# living.net
KiCad netlist of a schematic drawn in Altium Designer
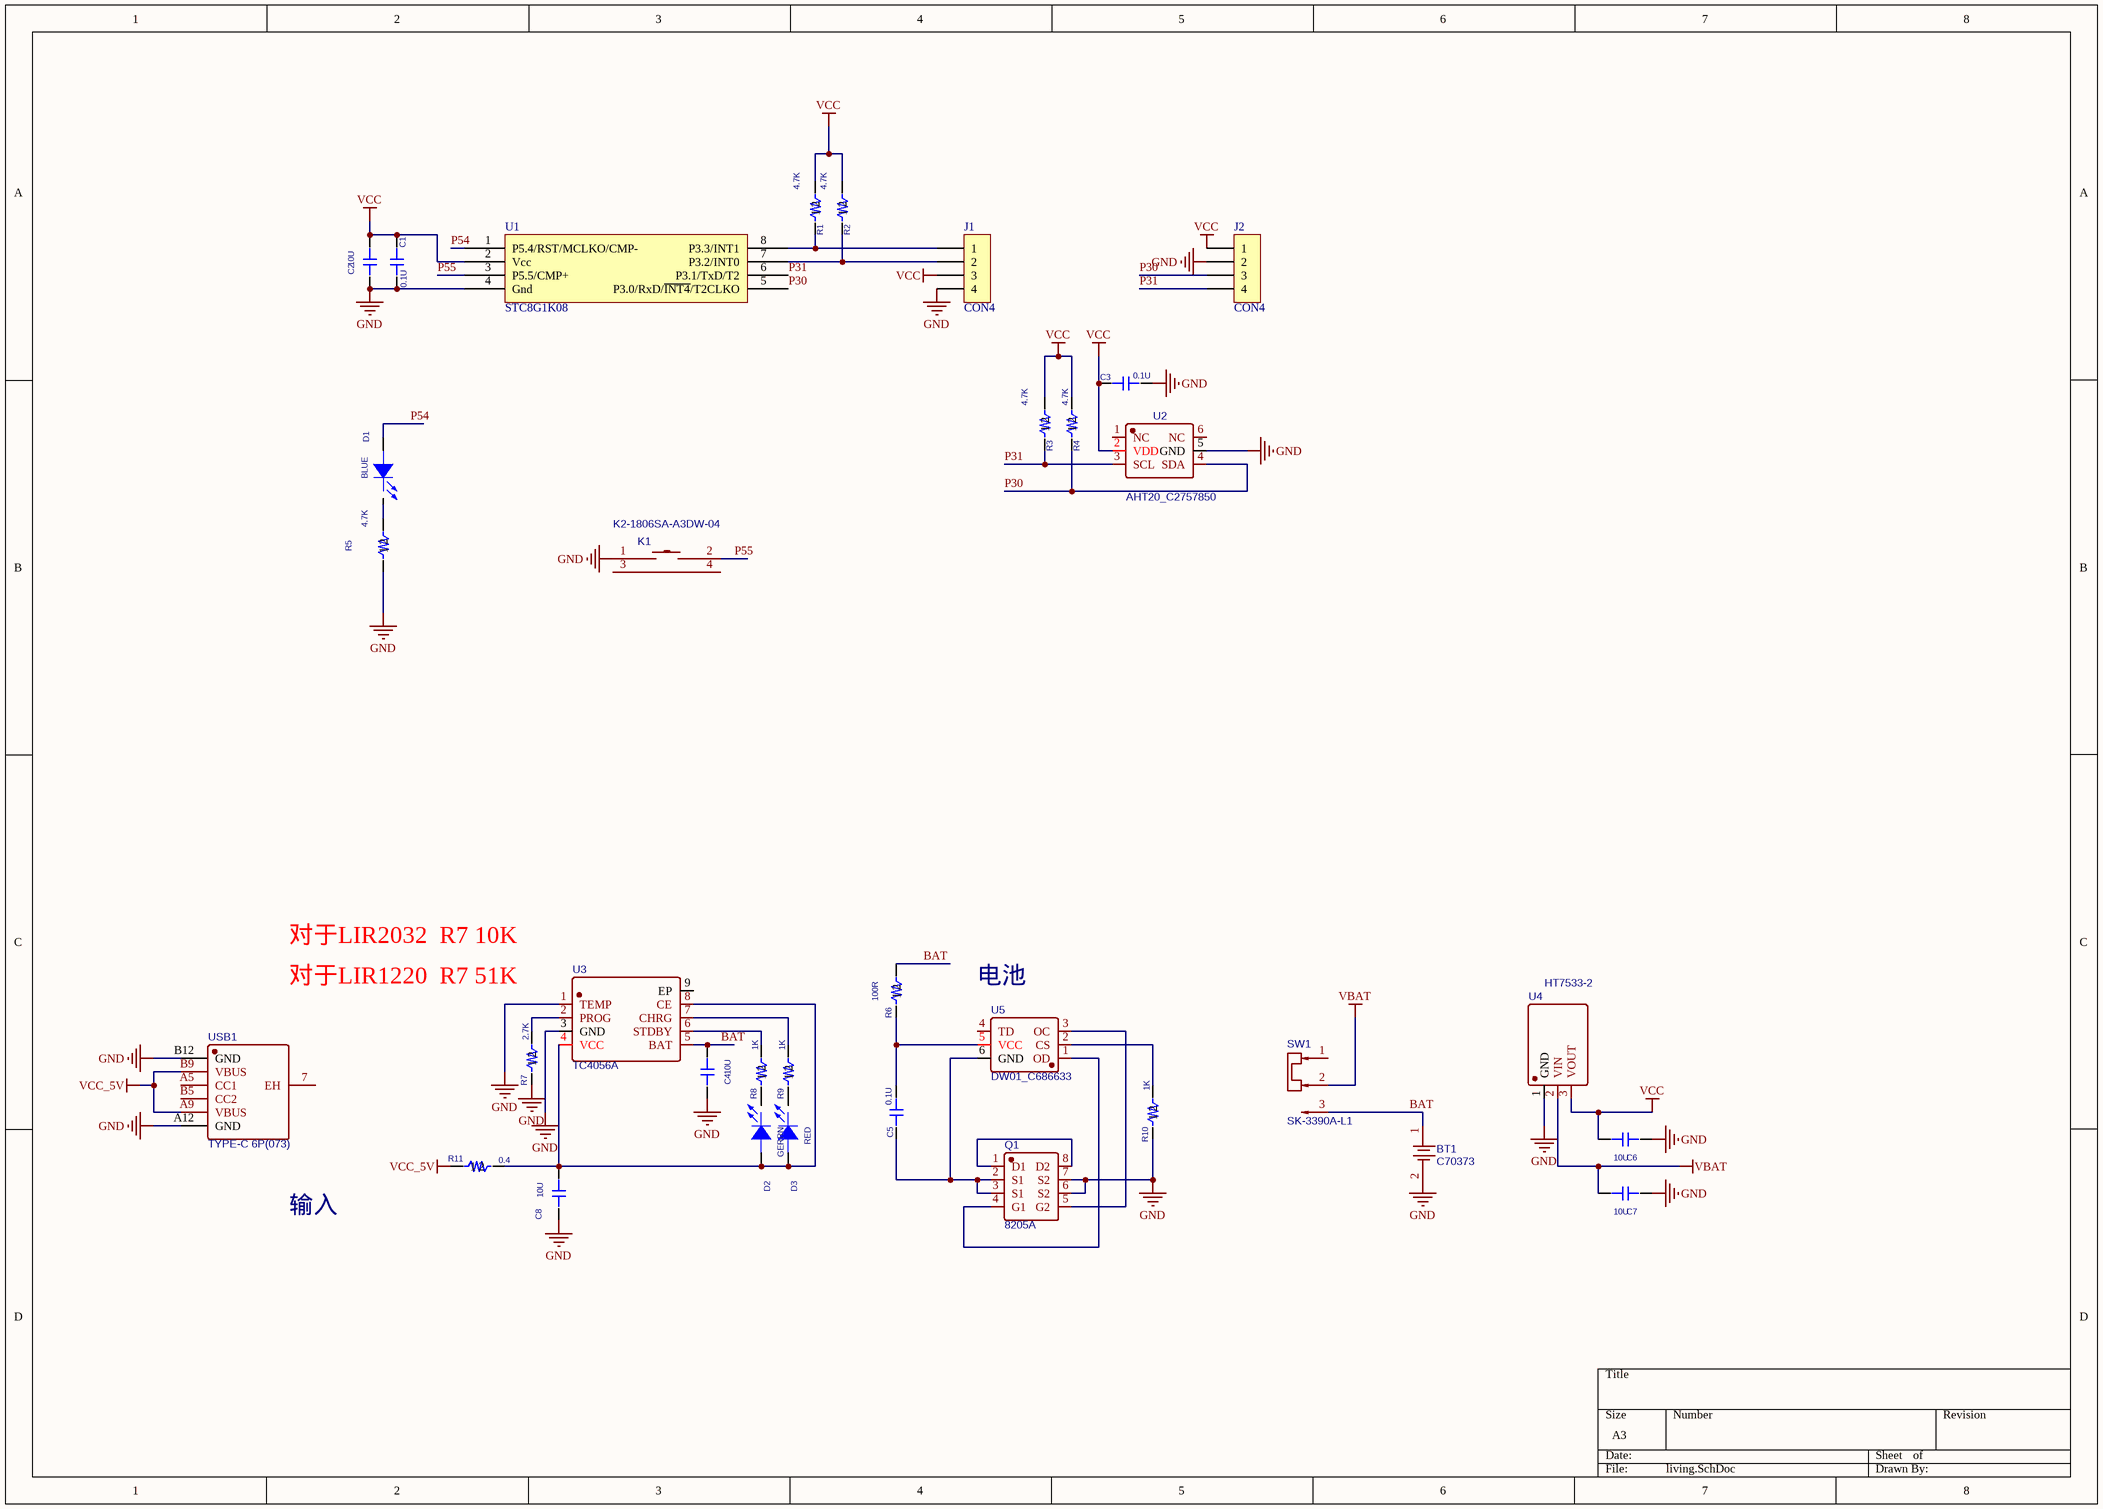
[diagram p0: living.SchDoc]

(export (version "E")
  (design (tool "Eeschema 10.0.6"))
  (components
    (comp (ref "BT1")
      (value "C70373")
      (footprint "BAT-SMD_CR2032-3V")
      (fields (field (name "CONTRIBUTOR") "LCSC"))
      (libsource (lib "CR2032") (part "C70373"))
    )
    (comp (ref "C1")
      (value "0.1U")
      (footprint "C_0603")
      (fields (field (name "Comment") "C_0.1UF_0603"))
      (libsource (lib "MINI-V3") (part "C_0.1UF_0603"))
    )
    (comp (ref "C2")
      (value "10U")
      (footprint "CAP_0603_FIRE")
      (fields (field (name "Comment") "C_10UF_0603"))
      (libsource (lib "MINI-V3") (part "C_10UF_0603"))
    )
    (comp (ref "C3")
      (value "0.1U")
      (footprint "C_0603")
      (fields (field (name "Comment") "C_0.1UF_0603"))
      (libsource (lib "MINI-V3") (part "C_0.1UF_0603"))
    )
    (comp (ref "C4")
      (value "10U")
      (footprint "CAP_0603_FIRE")
      (fields (field (name "Comment") "C_10UF_0603"))
      (libsource (lib "MINI-V3") (part "C_10UF_0603"))
    )
    (comp (ref "C5")
      (value "0.1U")
      (footprint "C_0603")
      (fields (field (name "Comment") "C_0.1UF_0603"))
      (libsource (lib "MINI-V3") (part "C_0.1UF_0603"))
    )
    (comp (ref "C6")
      (value "10U")
      (footprint "C_0603")
      (fields (field (name "Comment") "C_10UF_0603"))
      (libsource (lib "MINI-V3") (part "C_10UF_0603"))
    )
    (comp (ref "C7")
      (value "10U")
      (footprint "C_0603")
      (fields (field (name "Comment") "C_10UF_0603"))
      (libsource (lib "MINI-V3") (part "C_10UF_0603"))
    )
    (comp (ref "C8")
      (value "10U")
      (footprint "CAP_0603_FIRE")
      (fields (field (name "Comment") "C_10UF_0603"))
      (libsource (lib "MINI-V3") (part "C_10UF_0603"))
    )
    (comp (ref "D1")
      (value "BLUE")
      (footprint "LED_BLUE_0603_FIRE")
      (description "blue,0603")
      (fields (field (name "Comment") "LED_BLUE_0603_FIRE"))
      (libsource (lib "MINI-V3") (part "LED_BLUE_0603_FIRE"))
    )
    (comp (ref "D2")
      (value "GERRN")
      (footprint "LED_RED_0603_FIRE")
      (description "red,0805")
      (fields (field (name "Comment") "LED_RED_0603_FIRE"))
      (libsource (lib "MINI-V3") (part "LED_RED_0603_FIRE"))
    )
    (comp (ref "D3")
      (value "RED")
      (footprint "LED_RED_0603_FIRE")
      (description "red,0805")
      (fields (field (name "Comment") "LED_RED_0603_FIRE"))
      (libsource (lib "MINI-V3") (part "LED_RED_0603_FIRE"))
    )
    (comp (ref "J1")
      (value "CON4")
      (footprint "SIP-4")
      (description "Connector")
      (libsource (lib "CON系列") (part "CON4"))
    )
    (comp (ref "J2")
      (value "CON4")
      (footprint "SIP-4")
      (description "Connector")
      (libsource (lib "CON系列") (part "CON4"))
    )
    (comp (ref "K1")
      (value "K2-1806SA-A3DW-04")
      (footprint "KEY-SMD_K2-1806SA-AXXW-XX")
      (fields (field (name "BOM_SUPPLIER PART") "C2690015") (field (name "CONTRIBUTOR") "LCSC"))
      (libsource (lib "2_4_3.5按键") (part "K2-1806SA-A3DW-04"))
    )
    (comp (ref "Q1")
      (value "8205A")
      (footprint "TSSOP-8_L4.4-W3.0-P0.65-LS6.4-BL")
      (fields (field (name "BOM_SUPPLIER PART") "C181100") (field (name "CONTRIBUTOR") "LCSC"))
      (libsource (lib "8205A") (part "8205A"))
    )
    (comp (ref "R1")
      (value "4.7K")
      (footprint "RES_0603_FIRE")
      (description "0402")
      (fields (field (name "TOLERANCE") "+-5%") (field (name "Comment") "RES_4K7_0603_FIRE"))
      (libsource (lib "MINI-V3") (part "RES_4K7_0603_FIRE"))
    )
    (comp (ref "R2")
      (value "4.7K")
      (footprint "RES_0603_FIRE")
      (description "0402")
      (fields (field (name "TOLERANCE") "+-5%") (field (name "Comment") "RES_4K7_0603_FIRE"))
      (libsource (lib "MINI-V3") (part "RES_4K7_0603_FIRE"))
    )
    (comp (ref "R3")
      (value "4.7K")
      (footprint "RES_0603_FIRE")
      (description "0402")
      (fields (field (name "TOLERANCE") "+-5%") (field (name "Comment") "RES_4K7_0603_FIRE"))
      (libsource (lib "MINI-V3") (part "RES_4K7_0603_FIRE"))
    )
    (comp (ref "R4")
      (value "4.7K")
      (footprint "RES_0603_FIRE")
      (description "0402")
      (fields (field (name "TOLERANCE") "+-5%") (field (name "Comment") "RES_4K7_0603_FIRE"))
      (libsource (lib "MINI-V3") (part "RES_4K7_0603_FIRE"))
    )
    (comp (ref "R5")
      (value "4.7K")
      (footprint "RES_0603_FIRE")
      (description "0402")
      (fields (field (name "TOLERANCE") "+-5%") (field (name "Comment") "RES_4K7_0603_FIRE"))
      (libsource (lib "MINI-V3") (part "RES_4K7_0603_FIRE"))
    )
    (comp (ref "R6")
      (value "100R")
      (footprint "RES_0603_FIRE")
      (description "0402")
      (fields (field (name "TOLERANCE") "+-5%") (field (name "Comment") "RES_100R_0603_FIRE"))
      (libsource (lib "MINI-V3") (part "RES_100R_0603_FIRE"))
    )
    (comp (ref "R7")
      (value "2.7K")
      (footprint "R_0603")
      (fields (field (name "Comment") "R_2.7K_0603"))
      (libsource (lib "MINI-V3") (part "R_2.7K_0603"))
    )
    (comp (ref "R8")
      (value "1K")
      (footprint "RES_0603_FIRE")
      (description "0402")
      (fields (field (name "TOLERANCE") "+-5%") (field (name "Comment") "RES_1K_0603_FIRE"))
      (libsource (lib "MINI-V3") (part "RES_1K_0603_FIRE"))
    )
    (comp (ref "R9")
      (value "1K")
      (footprint "RES_0603_FIRE")
      (description "0402")
      (fields (field (name "TOLERANCE") "+-5%") (field (name "Comment") "RES_1K_0603_FIRE"))
      (libsource (lib "MINI-V3") (part "RES_1K_0603_FIRE"))
    )
    (comp (ref "R10")
      (value "1K")
      (footprint "RES_0603_FIRE")
      (description "0402")
      (fields (field (name "TOLERANCE") "+-5%") (field (name "Comment") "RES_1K_0603_FIRE"))
      (libsource (lib "MINI-V3") (part "RES_1K_0603_FIRE"))
    )
    (comp (ref "R11")
      (value "0.4")
      (footprint "R_0603")
      (fields (field (name "Comment") "R_2.7K_0603"))
      (libsource (lib "MINI-V3") (part "R_2.7K_0603"))
    )
    (comp (ref "SW1")
      (value "SK-3390A-L1")
      (footprint "SW-SMD_SK-3390A-L1")
      (fields (field (name "BOM_SUPPLIER PART") "C319018") (field (name "CONTRIBUTOR") "LCSC"))
      (libsource (lib "SK-3390A-L1") (part "SK-3390A-L1"))
    )
    (comp (ref "U1")
      (value "STC8G1K08")
      (footprint "SOP8")
      (libsource (lib "stcmcu_altium1819") (part "STC15W201S_SOP8"))
    )
    (comp (ref "U2")
      (value "AHT20_C2757850")
      (footprint "SENSOR-SMD_L3.0-W3.0-P1.00-BR")
      (fields
        (field (name "BOM_SUPPLIER PART") "C2757850")
        (field (name "BOM_MANUFACTURER PART") "AHT20")
        (field (name "CONTRIBUTOR") "LCSC")
      )
      (libsource (lib "AHT20") (part "AHT20_C2757850"))
    )
    (comp (ref "U3")
      (value "TC4056A")
      (footprint "SOP-8_L4.9-W3.9-P1.27-LS6.0-BL-EP")
      (fields (field (name "BOM_SUPPLIER PART") "C84051"))
      (libsource (lib "TC4056A") (part "TC4056A"))
    )
    (comp (ref "U4")
      (value "HT7533-2")
      (footprint "SOT-89-3_L4.5-W2.5-P1.50-LS4.2-BR")
      (fields (field (name "BOM_SUPPLIER PART") "C97849"))
      (libsource (lib "HT7533") (part "HT7533-2"))
    )
    (comp (ref "U5")
      (value "DW01_C686633")
      (footprint "SOT-23-6_L2.9-W1.6-P0.95-LS2.8-BR")
      (fields
        (field (name "BOM_SUPPLIER PART") "C686633")
        (field (name "BOM_MANUFACTURER PART") "DW01")
        (field (name "CONTRIBUTOR") "LCSC")
      )
      (libsource (lib "DW01") (part "DW01_C686633"))
    )
    (comp (ref "USB1")
      (value "TYPE-C 6P(073)")
      (footprint "TYPE-C-SMD_TYPE-C-6P")
      (fields (field (name "BOM_SUPPLIER PART") "C668623") (field (name "CONTRIBUTOR") "LCSC"))
      (libsource (lib "TYPE-C 6P(073)") (part "TYPE-C 6P(073)"))
    )
  )
  (nets
    (net (code "1") (name "/BAT") (class "Default")
      (node (ref "BT1") (pin "1") (pinfunction "1_1") (pintype "passive"))
      (node (ref "C4") (pin "2") (pinfunction "2_2") (pintype "passive"))
      (node (ref "R6") (pin "2") (pinfunction "2_2") (pintype "passive"))
      (node (ref "SW1") (pin "3") (pinfunction "3_3") (pintype "passive"))
      (node (ref "U3") (pin "5") (pinfunction "BAT_5") (pintype "passive"))
    )
    (net (code "2") (name "/P30") (class "Default")
      (node (ref "J2") (pin "3") (pinfunction "3_3") (pintype "passive"))
      (node (ref "R4") (pin "1") (pinfunction "1_1") (pintype "passive"))
      (node (ref "U1") (pin "5") (pinfunction "P3.0/RxD/~{INT4}/T2CLKO_5") (pintype "passive"))
      (node (ref "U2") (pin "4") (pinfunction "SDA_4") (pintype "passive"))
    )
    (net (code "3") (name "/P31") (class "Default")
      (node (ref "J2") (pin "4") (pinfunction "4_4") (pintype "passive"))
      (node (ref "R3") (pin "1") (pinfunction "1_1") (pintype "passive"))
      (node (ref "U1") (pin "6") (pinfunction "P3.1/TxD/T2_6") (pintype "passive"))
      (node (ref "U2") (pin "3") (pinfunction "SCL_3") (pintype "passive"))
    )
    (net (code "4") (name "/P54") (class "Default")
      (node (ref "D1") (pin "A") (pinfunction "ANODE_A") (pintype "passive"))
      (node (ref "U1") (pin "1") (pinfunction "P5.4/RST/MCLKO/CMP-_1") (pintype "passive"))
    )
    (net (code "5") (name "/P55") (class "Default")
      (node (ref "K1") (pin "2") (pinfunction "2_2") (pintype "passive"))
      (node (ref "U1") (pin "3") (pinfunction "P5.5/CMP+_3") (pintype "passive"))
    )
    (net (code "6") (name "GND") (class "Default")
      (node (ref "BT1") (pin "2") (pinfunction "2_2") (pintype "passive"))
      (node (ref "C1") (pin "2") (pinfunction "2_2") (pintype "passive"))
      (node (ref "C2") (pin "1") (pinfunction "1_1") (pintype "passive"))
      (node (ref "C3") (pin "2") (pinfunction "2_2") (pintype "passive"))
      (node (ref "C4") (pin "1") (pinfunction "1_1") (pintype "passive"))
      (node (ref "C6") (pin "1") (pinfunction "1_1") (pintype "passive"))
      (node (ref "C7") (pin "1") (pinfunction "1_1") (pintype "passive"))
      (node (ref "C8") (pin "1") (pinfunction "1_1") (pintype "passive"))
      (node (ref "J1") (pin "4") (pinfunction "4_4") (pintype "passive"))
      (node (ref "J2") (pin "2") (pinfunction "2_2") (pintype "passive"))
      (node (ref "K1") (pin "1") (pinfunction "1_1") (pintype "passive"))
      (node (ref "Q1") (pin "6") (pinfunction "S2_6") (pintype "passive"))
      (node (ref "Q1") (pin "7") (pinfunction "S2_7") (pintype "passive"))
      (node (ref "R10") (pin "1") (pinfunction "1_1") (pintype "passive"))
      (node (ref "R5") (pin "1") (pinfunction "1_1") (pintype "passive"))
      (node (ref "R7") (pin "1") (pinfunction "1_1") (pintype "passive"))
      (node (ref "U1") (pin "4") (pinfunction "Gnd_4") (pintype "passive"))
      (node (ref "U2") (pin "5") (pinfunction "GND_5") (pintype "passive"))
      (node (ref "U3") (pin "1") (pinfunction "TEMP_1") (pintype "passive"))
      (node (ref "U3") (pin "3") (pinfunction "GND_3") (pintype "passive"))
      (node (ref "U4") (pin "1") (pinfunction "GND_1") (pintype "passive"))
      (node (ref "USB1") (pin "A12") (pinfunction "GND_A12") (pintype "passive"))
      (node (ref "USB1") (pin "B12") (pinfunction "GND_B12") (pintype "passive"))
    )
    (net (code "7") (name "Net-(D1-CATHODE)") (class "Default")
      (node (ref "D1") (pin "K") (pinfunction "CATHODE_K") (pintype "passive"))
      (node (ref "R5") (pin "2") (pinfunction "2_2") (pintype "passive"))
    )
    (net (code "8") (name "Net-(D2-ANODE)") (class "Default")
      (node (ref "C8") (pin "2") (pinfunction "2_2") (pintype "passive"))
      (node (ref "D2") (pin "A") (pinfunction "ANODE_A") (pintype "passive"))
      (node (ref "D3") (pin "A") (pinfunction "ANODE_A") (pintype "passive"))
      (node (ref "R11") (pin "2") (pinfunction "2_2") (pintype "passive"))
      (node (ref "U3") (pin "4") (pinfunction "VCC_4") (pintype "passive"))
      (node (ref "U3") (pin "8") (pinfunction "CE_8") (pintype "passive"))
    )
    (net (code "9") (name "Net-(D2-CATHODE)") (class "Default")
      (node (ref "D2") (pin "K") (pinfunction "CATHODE_K") (pintype "passive"))
      (node (ref "R8") (pin "1") (pinfunction "1_1") (pintype "passive"))
    )
    (net (code "10") (name "Net-(D3-CATHODE)") (class "Default")
      (node (ref "D3") (pin "K") (pinfunction "CATHODE_K") (pintype "passive"))
      (node (ref "R9") (pin "1") (pinfunction "1_1") (pintype "passive"))
    )
    (net (code "11") (name "Net-(Q1-D1)") (class "Default")
      (node (ref "Q1") (pin "1") (pinfunction "D1_1") (pintype "passive"))
      (node (ref "Q1") (pin "8") (pinfunction "D2_8") (pintype "passive"))
    )
    (net (code "12") (name "Net-(Q1-G1)") (class "Default")
      (node (ref "Q1") (pin "4") (pinfunction "G1_4") (pintype "passive"))
      (node (ref "U5") (pin "1") (pinfunction "OD_1") (pintype "passive"))
    )
    (net (code "13") (name "Net-(Q1-G2)") (class "Default")
      (node (ref "Q1") (pin "5") (pinfunction "G2_5") (pintype "passive"))
      (node (ref "U5") (pin "3") (pinfunction "OC_3") (pintype "passive"))
    )
    (net (code "14") (name "Net-(U1-P3.2{slash}INT0)") (class "Default")
      (node (ref "J1") (pin "2") (pinfunction "2_2") (pintype "passive"))
      (node (ref "R2") (pin "1") (pinfunction "1_1") (pintype "passive"))
      (node (ref "U1") (pin "7") (pinfunction "P3.2/INT0_7") (pintype "passive"))
    )
    (net (code "15") (name "Net-(U1-P3.3{slash}INT1)") (class "Default")
      (node (ref "J1") (pin "1") (pinfunction "1_1") (pintype "passive"))
      (node (ref "R1") (pin "1") (pinfunction "1_1") (pintype "passive"))
      (node (ref "U1") (pin "8") (pinfunction "P3.3/INT1_8") (pintype "passive"))
    )
    (net (code "16") (name "Net-(U3-CHRG)") (class "Default")
      (node (ref "R9") (pin "2") (pinfunction "2_2") (pintype "passive"))
      (node (ref "U3") (pin "7") (pinfunction "CHRG_7") (pintype "passive"))
    )
    (net (code "17") (name "Net-(U3-PROG)") (class "Default")
      (node (ref "R7") (pin "2") (pinfunction "2_2") (pintype "passive"))
      (node (ref "U3") (pin "2") (pinfunction "PROG_2") (pintype "passive"))
    )
    (net (code "18") (name "Net-(U3-STDBY)") (class "Default")
      (node (ref "R8") (pin "2") (pinfunction "2_2") (pintype "passive"))
      (node (ref "U3") (pin "6") (pinfunction "STDBY_6") (pintype "passive"))
    )
    (net (code "19") (name "Net-(U5-CS)") (class "Default")
      (node (ref "R10") (pin "2") (pinfunction "2_2") (pintype "passive"))
      (node (ref "U5") (pin "2") (pinfunction "CS_2") (pintype "passive"))
    )
    (net (code "20") (name "Net-(U5-GND)") (class "Default")
      (node (ref "C5") (pin "1") (pinfunction "1_1") (pintype "passive"))
      (node (ref "Q1") (pin "2") (pinfunction "S1_2") (pintype "passive"))
      (node (ref "Q1") (pin "3") (pinfunction "S1_3") (pintype "passive"))
      (node (ref "U5") (pin "6") (pinfunction "GND_6") (pintype "passive"))
    )
    (net (code "21") (name "Net-(U5-VCC)") (class "Default")
      (node (ref "C5") (pin "2") (pinfunction "2_2") (pintype "passive"))
      (node (ref "R6") (pin "1") (pinfunction "1_1") (pintype "passive"))
      (node (ref "U5") (pin "5") (pinfunction "VCC_5") (pintype "passive"))
    )
    (net (code "22") (name "VBAT") (class "Default")
      (node (ref "C7") (pin "2") (pinfunction "2_2") (pintype "passive"))
      (node (ref "SW1") (pin "2") (pinfunction "2_2") (pintype "passive"))
      (node (ref "U4") (pin "2") (pinfunction "VIN_2") (pintype "passive"))
    )
    (net (code "23") (name "VCC") (class "Default")
      (node (ref "C1") (pin "1") (pinfunction "1_1") (pintype "passive"))
      (node (ref "C2") (pin "2") (pinfunction "2_2") (pintype "passive"))
      (node (ref "C3") (pin "1") (pinfunction "1_1") (pintype "passive"))
      (node (ref "C6") (pin "2") (pinfunction "2_2") (pintype "passive"))
      (node (ref "J1") (pin "3") (pinfunction "3_3") (pintype "passive"))
      (node (ref "J2") (pin "1") (pinfunction "1_1") (pintype "passive"))
      (node (ref "R1") (pin "2") (pinfunction "2_2") (pintype "passive"))
      (node (ref "R2") (pin "2") (pinfunction "2_2") (pintype "passive"))
      (node (ref "R3") (pin "2") (pinfunction "2_2") (pintype "passive"))
      (node (ref "R4") (pin "2") (pinfunction "2_2") (pintype "passive"))
      (node (ref "U1") (pin "2") (pinfunction "Vcc_2") (pintype "passive"))
      (node (ref "U2") (pin "2") (pinfunction "VDD_2") (pintype "passive"))
      (node (ref "U4") (pin "3") (pinfunction "VOUT_3") (pintype "passive"))
    )
    (net (code "24") (name "VCC_5V") (class "Default")
      (node (ref "R11") (pin "1") (pinfunction "1_1") (pintype "passive"))
      (node (ref "USB1") (pin "A9") (pinfunction "VBUS_A9") (pintype "passive"))
      (node (ref "USB1") (pin "B9") (pinfunction "VBUS_B9") (pintype "passive"))
    )
    (net (code "25") (name "unconnected-(K1-Pad3)") (class "Default")
      (node (ref "K1") (pin "3") (pinfunction "3_3") (pintype "passive"))
    )
    (net (code "26") (name "unconnected-(K1-Pad4)") (class "Default")
      (node (ref "K1") (pin "4") (pinfunction "4_4") (pintype "passive"))
    )
    (net (code "27") (name "unconnected-(SW1-Pad1)") (class "Default")
      (node (ref "SW1") (pin "1") (pinfunction "1_1") (pintype "passive"))
    )
    (net (code "28") (name "unconnected-(U2-NC-Pad1)") (class "Default")
      (node (ref "U2") (pin "1") (pinfunction "NC_1") (pintype "passive"))
    )
    (net (code "29") (name "unconnected-(U2-NC-Pad6)") (class "Default")
      (node (ref "U2") (pin "6") (pinfunction "NC_6") (pintype "passive"))
    )
    (net (code "30") (name "unconnected-(U3-EP-Pad9)") (class "Default")
      (node (ref "U3") (pin "9") (pinfunction "EP_9") (pintype "passive"))
    )
    (net (code "31") (name "unconnected-(U5-TD-Pad4)") (class "Default")
      (node (ref "U5") (pin "4") (pinfunction "TD_4") (pintype "passive"))
    )
    (net (code "32") (name "unconnected-(USB1-CC1-PadA5)") (class "Default")
      (node (ref "USB1") (pin "A5") (pinfunction "CC1_A5") (pintype "passive"))
    )
    (net (code "33") (name "unconnected-(USB1-CC2-PadB5)") (class "Default")
      (node (ref "USB1") (pin "B5") (pinfunction "CC2_B5") (pintype "passive"))
    )
    (net (code "34") (name "unconnected-(USB1-EH-Pad7)") (class "Default")
      (node (ref "USB1") (pin "7") (pinfunction "EH_7") (pintype "passive"))
    )
  )
)
